# fermentasi.net
KiCad netlist of a schematic drawn in EAGLE
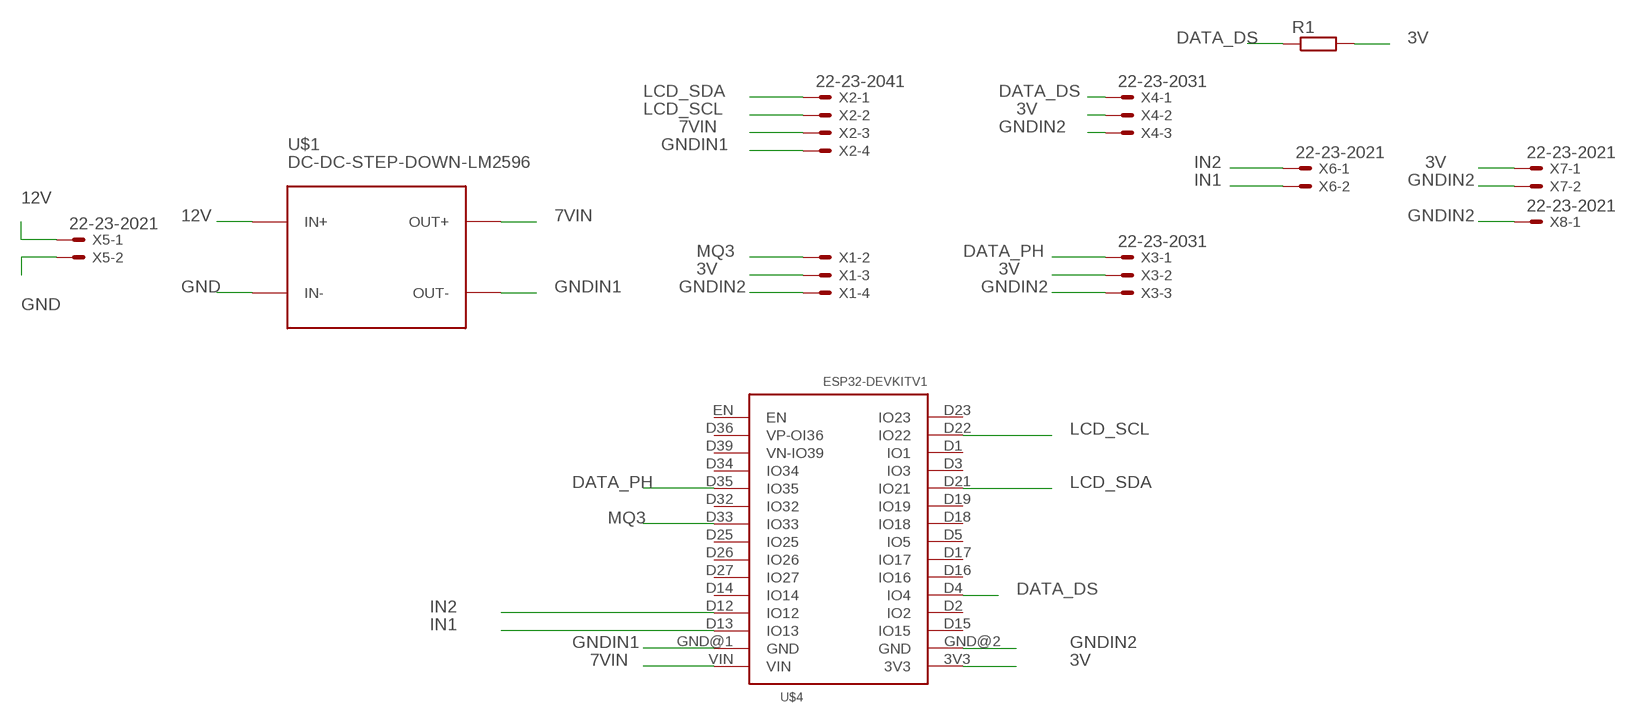
[diagram p0: schematic, sheet 1]

(export (version "E")
  (design (tool "Eeschema 10.0.6"))
  (components
    (comp (ref "R1")
      (value "R-EU_0207/10")
      (footprint "eagle-import:0207_10")
      (libsource (lib "eagle-import") (part "R-EU_0207/10"))
    )
    (comp (ref "U$1")
      (value "DC-DC-STEP-DOWN-LM2596")
      (footprint "eagle-import:DC-DC-STEP-DOWN-LM2596")
      (libsource (lib "eagle-import") (part "DC-DC-STEP-DOWN-LM2596"))
    )
    (comp (ref "U$4")
      (value "ESP32DEVKITV1")
      (footprint "eagle-import:ESP32-DEVKITV1")
      (libsource (lib "eagle-import") (part "ESP32DEVKITV1"))
    )
    (comp (ref "X1")
      (value "22-23-2041")
      (footprint "eagle-import:22-23-2041")
      (fields (field (name "MF") "MOLEX"))
      (libsource (lib "eagle-import") (part "22-23-2041"))
    )
    (comp (ref "X2")
      (value "22-23-2041")
      (footprint "eagle-import:22-23-2041")
      (fields (field (name "MF") "MOLEX"))
      (libsource (lib "eagle-import") (part "22-23-2041"))
    )
    (comp (ref "X3")
      (value "22-23-2031")
      (footprint "eagle-import:22-23-2031")
      (fields (field (name "MF") "MOLEX"))
      (libsource (lib "eagle-import") (part "22-23-2031"))
    )
    (comp (ref "X4")
      (value "22-23-2031")
      (footprint "eagle-import:22-23-2031")
      (fields (field (name "MF") "MOLEX"))
      (libsource (lib "eagle-import") (part "22-23-2031"))
    )
    (comp (ref "X5")
      (value "22-23-2021")
      (footprint "eagle-import:22-23-2021")
      (fields (field (name "MF") "MOLEX"))
      (libsource (lib "eagle-import") (part "22-23-2021"))
    )
    (comp (ref "X6")
      (value "22-23-2021")
      (footprint "eagle-import:22-23-2021")
      (fields (field (name "MF") "MOLEX"))
      (libsource (lib "eagle-import") (part "22-23-2021"))
    )
    (comp (ref "X7")
      (value "22-23-2021")
      (footprint "eagle-import:22-23-2021")
      (fields (field (name "MF") "MOLEX"))
      (libsource (lib "eagle-import") (part "22-23-2021"))
    )
    (comp (ref "X8")
      (value "22-23-2021")
      (footprint "eagle-import:22-23-2021")
      (fields (field (name "MF") "MOLEX"))
      (libsource (lib "eagle-import") (part "22-23-2021"))
    )
  )
  (nets
    (net (code "1") (name "/3V") (class "Default")
      (node (ref "R1") (pin "2") (pinfunction "2_2") (pintype "passive"))
      (node (ref "U$4") (pin "3V3") (pinfunction "3V3_3V3") (pintype "bidirectional"))
      (node (ref "X1") (pin "3") (pinfunction "S_3") (pintype "passive"))
      (node (ref "X3") (pin "2") (pinfunction "S_2") (pintype "passive"))
      (node (ref "X4") (pin "2") (pinfunction "S_2") (pintype "passive"))
      (node (ref "X7") (pin "1") (pinfunction "S_1") (pintype "passive"))
    )
    (net (code "2") (name "/7VIN") (class "Default")
      (node (ref "U$1") (pin "OUT+") (pinfunction "OUT+_OUT+") (pintype "bidirectional"))
      (node (ref "U$4") (pin "VIN") (pinfunction "VIN_VIN") (pintype "bidirectional"))
      (node (ref "X2") (pin "3") (pinfunction "S_3") (pintype "passive"))
    )
    (net (code "3") (name "/12V") (class "Default")
      (node (ref "U$1") (pin "IN+") (pinfunction "IN+_IN+") (pintype "bidirectional"))
      (node (ref "X5") (pin "1") (pinfunction "S_1") (pintype "passive"))
    )
    (net (code "4") (name "/DATA_DS") (class "Default")
      (node (ref "R1") (pin "1") (pinfunction "1_1") (pintype "passive"))
      (node (ref "U$4") (pin "D4") (pinfunction "IO4_D4") (pintype "bidirectional"))
      (node (ref "X4") (pin "1") (pinfunction "S_1") (pintype "passive"))
    )
    (net (code "5") (name "/DATA_PH") (class "Default")
      (node (ref "U$4") (pin "D35") (pinfunction "IO35_D35") (pintype "bidirectional"))
      (node (ref "X3") (pin "1") (pinfunction "S_1") (pintype "passive"))
    )
    (net (code "6") (name "/GND") (class "Default")
      (node (ref "U$1") (pin "IN-") (pinfunction "IN-_IN-") (pintype "bidirectional"))
      (node (ref "X5") (pin "2") (pinfunction "S_2") (pintype "passive"))
    )
    (net (code "7") (name "/GNDIN1") (class "Default")
      (node (ref "U$1") (pin "OUT-") (pinfunction "OUT-_OUT-") (pintype "bidirectional"))
      (node (ref "U$4") (pin "GND@1") (pinfunction "GND_GND@1") (pintype "bidirectional"))
      (node (ref "X2") (pin "4") (pinfunction "S_4") (pintype "passive"))
    )
    (net (code "8") (name "/GNDIN2") (class "Default")
      (node (ref "U$4") (pin "GND@2") (pinfunction "GND_GND@2") (pintype "bidirectional"))
      (node (ref "X1") (pin "4") (pinfunction "S_4") (pintype "passive"))
      (node (ref "X3") (pin "3") (pinfunction "S_3") (pintype "passive"))
      (node (ref "X4") (pin "3") (pinfunction "S_3") (pintype "passive"))
      (node (ref "X7") (pin "2") (pinfunction "S_2") (pintype "passive"))
      (node (ref "X8") (pin "1") (pinfunction "S_1") (pintype "passive"))
    )
    (net (code "9") (name "/IN1") (class "Default")
      (node (ref "U$4") (pin "D13") (pinfunction "IO13_D13") (pintype "bidirectional"))
      (node (ref "X6") (pin "2") (pinfunction "S_2") (pintype "passive"))
    )
    (net (code "10") (name "/IN2") (class "Default")
      (node (ref "U$4") (pin "D12") (pinfunction "IO12_D12") (pintype "bidirectional"))
      (node (ref "X6") (pin "1") (pinfunction "S_1") (pintype "passive"))
    )
    (net (code "11") (name "/LCD_SCL") (class "Default")
      (node (ref "U$4") (pin "D22") (pinfunction "IO22_D22") (pintype "bidirectional"))
      (node (ref "X2") (pin "2") (pinfunction "S_2") (pintype "passive"))
    )
    (net (code "12") (name "/LCD_SDA") (class "Default")
      (node (ref "U$4") (pin "D21") (pinfunction "IO21_D21") (pintype "bidirectional"))
      (node (ref "X2") (pin "1") (pinfunction "S_1") (pintype "passive"))
    )
    (net (code "13") (name "/MQ3") (class "Default")
      (node (ref "U$4") (pin "D33") (pinfunction "IO33_D33") (pintype "bidirectional"))
      (node (ref "X1") (pin "2") (pinfunction "S_2") (pintype "passive"))
    )
    (net (code "14") (name "unconnected-(U$4-IO1-PadD1)") (class "Default")
      (node (ref "U$4") (pin "D1") (pinfunction "IO1_D1") (pintype "bidirectional"))
    )
    (net (code "15") (name "unconnected-(U$4-IO2-PadD2)") (class "Default")
      (node (ref "U$4") (pin "D2") (pinfunction "IO2_D2") (pintype "bidirectional"))
    )
    (net (code "16") (name "unconnected-(U$4-IO3-PadD3)") (class "Default")
      (node (ref "U$4") (pin "D3") (pinfunction "IO3_D3") (pintype "bidirectional"))
    )
    (net (code "17") (name "unconnected-(U$4-IO5-PadD5)") (class "Default")
      (node (ref "U$4") (pin "D5") (pinfunction "IO5_D5") (pintype "bidirectional"))
    )
    (net (code "18") (name "unconnected-(U$4-IO14-PadD14)") (class "Default")
      (node (ref "U$4") (pin "D14") (pinfunction "IO14_D14") (pintype "bidirectional"))
    )
    (net (code "19") (name "unconnected-(U$4-IO15-PadD15)") (class "Default")
      (node (ref "U$4") (pin "D15") (pinfunction "IO15_D15") (pintype "bidirectional"))
    )
    (net (code "20") (name "unconnected-(U$4-IO16-PadD16)") (class "Default")
      (node (ref "U$4") (pin "D16") (pinfunction "IO16_D16") (pintype "bidirectional"))
    )
    (net (code "21") (name "unconnected-(U$4-IO17-PadD17)") (class "Default")
      (node (ref "U$4") (pin "D17") (pinfunction "IO17_D17") (pintype "bidirectional"))
    )
    (net (code "22") (name "unconnected-(U$4-IO18-PadD18)") (class "Default")
      (node (ref "U$4") (pin "D18") (pinfunction "IO18_D18") (pintype "bidirectional"))
    )
    (net (code "23") (name "unconnected-(U$4-IO19-PadD19)") (class "Default")
      (node (ref "U$4") (pin "D19") (pinfunction "IO19_D19") (pintype "bidirectional"))
    )
    (net (code "24") (name "unconnected-(U$4-IO23-PadD23)") (class "Default")
      (node (ref "U$4") (pin "D23") (pinfunction "IO23_D23") (pintype "bidirectional"))
    )
    (net (code "25") (name "unconnected-(U$4-IO25-PadD25)") (class "Default")
      (node (ref "U$4") (pin "D25") (pinfunction "IO25_D25") (pintype "bidirectional"))
    )
    (net (code "26") (name "unconnected-(U$4-IO26-PadD26)") (class "Default")
      (node (ref "U$4") (pin "D26") (pinfunction "IO26_D26") (pintype "bidirectional"))
    )
    (net (code "27") (name "unconnected-(U$4-IO27-PadD27)") (class "Default")
      (node (ref "U$4") (pin "D27") (pinfunction "IO27_D27") (pintype "bidirectional"))
    )
    (net (code "28") (name "unconnected-(U$4-IO32-PadD32)") (class "Default")
      (node (ref "U$4") (pin "D32") (pinfunction "IO32_D32") (pintype "bidirectional"))
    )
    (net (code "29") (name "unconnected-(U$4-IO34-PadD34)") (class "Default")
      (node (ref "U$4") (pin "D34") (pinfunction "IO34_D34") (pintype "bidirectional"))
    )
    (net (code "30") (name "unconnected-(U$4-PadEN)") (class "Default")
      (node (ref "U$4") (pin "EN") (pinfunction "EN_EN") (pintype "bidirectional"))
    )
    (net (code "31") (name "unconnected-(U$4-VN-IO39-PadD39)") (class "Default")
      (node (ref "U$4") (pin "D39") (pinfunction "VN-IO39_D39") (pintype "bidirectional"))
    )
    (net (code "32") (name "unconnected-(U$4-VP-OI36-PadD36)") (class "Default")
      (node (ref "U$4") (pin "D36") (pinfunction "VP-OI36_D36") (pintype "bidirectional"))
    )
  )
)
